# Sheet3.net
KiCad netlist of a schematic drawn in Altium Designer
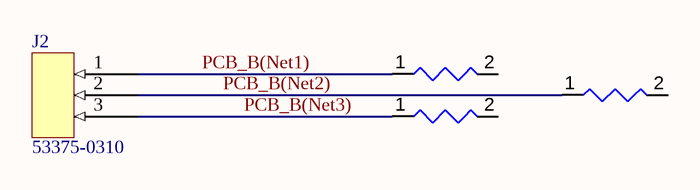
[diagram p0: Sheet3.SchDoc]

(export (version "E")
  (design (tool "Eeschema 10.0.6"))
  (components
    (comp (ref "J2")
      (value "53375-0310")
      (footprint "PCB1:SOJ127P870X356-20M")
      (fields (field (name "MANUFACTURER") "Molex"))
      (libsource (lib "SCH") (part "CMP-002-00074-2"))
    )
    (comp (ref "R1")
      (value "Resistor 10k +/-1% 1206 250 mW")
      (footprint "RESC3216X60X45ML15T20")
      (description "Chip Resistor, 10 KOhm, +/- 1%, 0.25 W, -55 to 155 degC, 1206 (3216 Metric)")
      (fields (field (name "TOLERANCE") "1%") (field (name "POWER") "250mW"))
      (libsource (lib "SCH") (part "RES-2"))
    )
    (comp (ref "R2")
      (value "Resistor 10k +/-1% 1206 250 mW")
      (footprint "RESC3216X60X45ML15T20")
      (description "Chip Resistor, 10 KOhm, +/- 1%, 0.25 W, -55 to 155 degC, 1206 (3216 Metric)")
      (fields (field (name "TOLERANCE") "1%") (field (name "POWER") "250mW"))
      (libsource (lib "SCH") (part "RES-2"))
    )
    (comp (ref "R3")
      (value "Resistor 10k +/-1% 1206 250 mW")
      (footprint "RESC3216X60X45ML15T20")
      (description "Chip Resistor, 10 KOhm, +/- 1%, 0.25 W, -55 to 155 degC, 1206 (3216 Metric)")
      (fields (field (name "TOLERANCE") "1%") (field (name "POWER") "250mW"))
      (libsource (lib "SCH") (part "RES-2"))
    )
  )
  (nets
    (net (code "1") (name "/PCB_B(Net1)") (class "Default")
      (node (ref "J2") (pin "1") (pinfunction "1_1") (pintype "input"))
      (node (ref "R1") (pin "1") (pinfunction "1_1") (pintype "passive"))
    )
    (net (code "2") (name "/PCB_B(Net2)") (class "Default")
      (node (ref "J2") (pin "2") (pinfunction "2_2") (pintype "input"))
      (node (ref "R2") (pin "1") (pinfunction "1_1") (pintype "passive"))
    )
    (net (code "3") (name "/PCB_B(Net3)") (class "Default")
      (node (ref "J2") (pin "3") (pinfunction "3_3") (pintype "input"))
      (node (ref "R3") (pin "1") (pinfunction "1_1") (pintype "passive"))
    )
    (net (code "4") (name "unconnected-(R1-Pad2)") (class "Default")
      (node (ref "R1") (pin "2") (pinfunction "2_2") (pintype "passive"))
    )
    (net (code "5") (name "unconnected-(R2-Pad2)") (class "Default")
      (node (ref "R2") (pin "2") (pinfunction "2_2") (pintype "passive"))
    )
    (net (code "6") (name "unconnected-(R3-Pad2)") (class "Default")
      (node (ref "R3") (pin "2") (pinfunction "2_2") (pintype "passive"))
    )
  )
)
